# UVBox-I2C_LCD.net
KiCad netlist of a schematic drawn in EAGLE
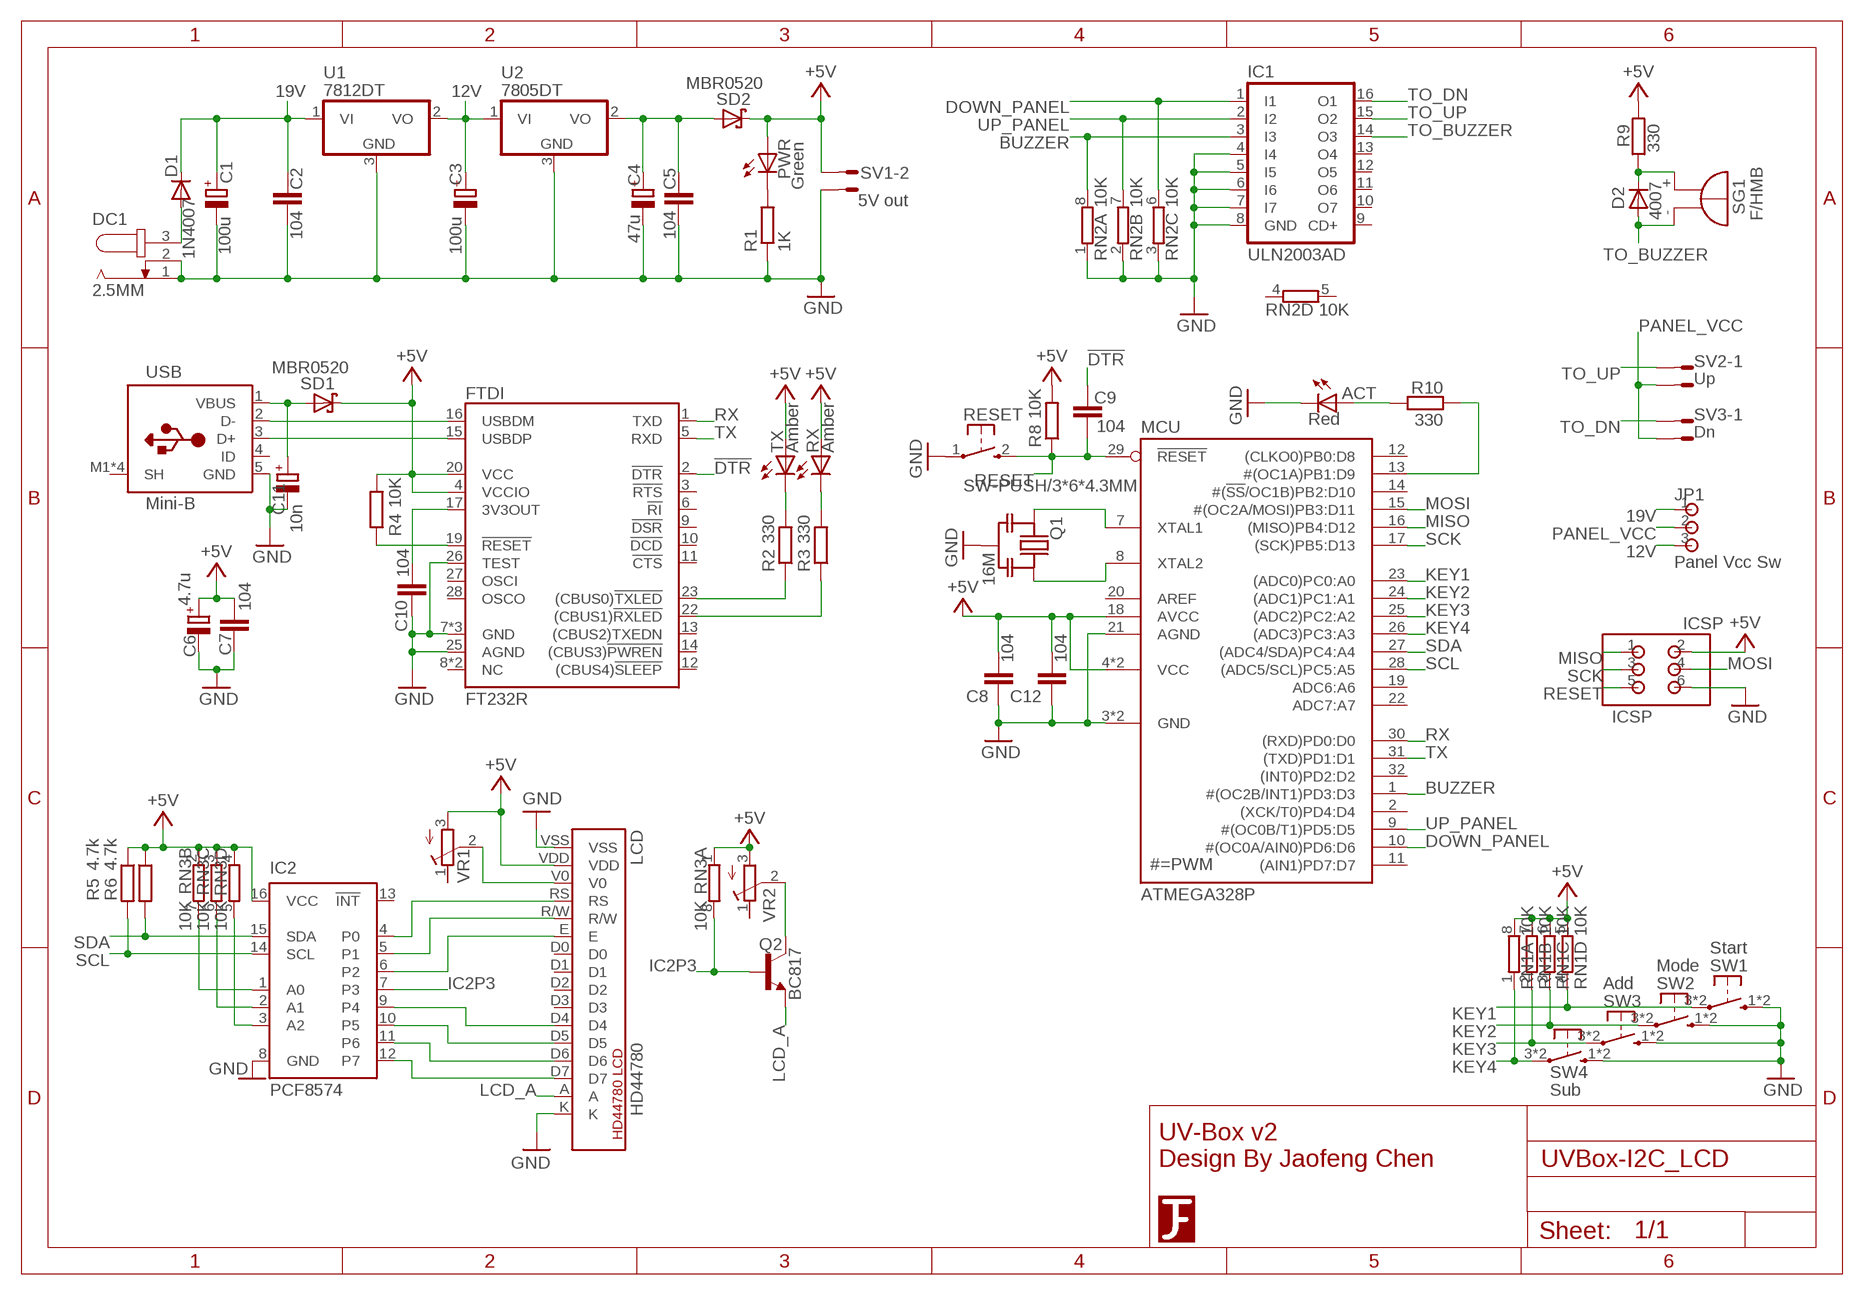
[diagram p0: schematic, sheet 1]

(export (version "E")
  (design (tool "Eeschema 10.0.6"))
  (components
    (comp (ref "ACT")
      (value "Red")
      (footprint "eagle-import:CHIPLED_0805")
      (libsource (lib "eagle-import") (part "LEDCHIPLED_0805"))
    )
    (comp (ref "C1")
      (value "100u")
      (footprint "eagle-import:140CLH-0810")
      (libsource (lib "eagle-import") (part "CPOL-EU140CLH-0810"))
    )
    (comp (ref "C2")
      (value "104")
      (footprint "eagle-import:C0805")
      (libsource (lib "eagle-import") (part "C-EUC0805"))
    )
    (comp (ref "C3")
      (value "100u")
      (footprint "eagle-import:SMC_C")
      (libsource (lib "eagle-import") (part "CPOL-EUSMCC"))
    )
    (comp (ref "C4")
      (value "47u")
      (footprint "eagle-import:SMC_C")
      (libsource (lib "eagle-import") (part "CPOL-EUSMCC"))
    )
    (comp (ref "C5")
      (value "104")
      (footprint "eagle-import:C0805")
      (libsource (lib "eagle-import") (part "C-EUC0805"))
    )
    (comp (ref "C6")
      (value "4.7u")
      (footprint "eagle-import:SMC_B")
      (libsource (lib "eagle-import") (part "CPOL-EUSMCB"))
    )
    (comp (ref "C7")
      (value "104")
      (footprint "eagle-import:C0603")
      (libsource (lib "eagle-import") (part "C-EUC0603"))
    )
    (comp (ref "C8")
      (value "104")
      (footprint "eagle-import:C0603")
      (libsource (lib "eagle-import") (part "C-EUC0603"))
    )
    (comp (ref "C9")
      (value "104")
      (footprint "eagle-import:C0603")
      (libsource (lib "eagle-import") (part "C-EUC0603"))
    )
    (comp (ref "C10")
      (value "104")
      (footprint "eagle-import:C0603")
      (libsource (lib "eagle-import") (part "C-EUC0603"))
    )
    (comp (ref "C11")
      (value "10n")
      (footprint "eagle-import:SMC_A")
      (libsource (lib "eagle-import") (part "CPOL-EUSMCA"))
    )
    (comp (ref "C12")
      (value "104")
      (footprint "eagle-import:C0603")
      (libsource (lib "eagle-import") (part "C-EUC0603"))
    )
    (comp (ref "D1")
      (value "1N4007")
      (footprint "eagle-import:DO-214AC")
      (libsource (lib "eagle-import") (part "DIODE-DO-214AC"))
    )
    (comp (ref "D2")
      (value "4007")
      (footprint "eagle-import:DO214AA")
      (libsource (lib "eagle-import") (part "DIODE-DO214AA"))
    )
    (comp (ref "DC1")
      (value "2.5MM")
      (footprint "eagle-import:SPC4078")
      (libsource (lib "eagle-import") (part "DC-JACK/2.5MM"))
    )
    (comp (ref "FTDI")
      (value "FT232R")
      (footprint "eagle-import:SSOP28")
      (libsource (lib "eagle-import") (part "FT232R"))
    )
    (comp (ref "IC1")
      (value "ULN2003AD")
      (footprint "eagle-import:SO16(R-PDSO-G16)")
      (libsource (lib "eagle-import") (part "ULN2003AD"))
    )
    (comp (ref "IC2")
      (value "PCF8574")
      (footprint "eagle-import:SO16W")
      (libsource (lib "eagle-import") (part "PCF8574/SO16W"))
    )
    (comp (ref "ICSP")
      (value "ICSP")
      (footprint "eagle-import:DIP-2.54-2X3")
      (libsource (lib "eagle-import") (part "PIN-2X3/2.54-DIP"))
    )
    (comp (ref "JP1")
      (value "Panel Vcc Sw")
      (footprint "eagle-import:DIP-2.54-1X3")
      (libsource (lib "eagle-import") (part "PIN-1X3-2.54"))
    )
    (comp (ref "LCD")
      (value "HD44780")
      (footprint "eagle-import:LCD_1602")
      (libsource (lib "eagle-import") (part "LCD-HD44780-1602"))
    )
    (comp (ref "MCU")
      (value "ATMEGA328P")
      (footprint "eagle-import:TQFP32")
      (libsource (lib "eagle-import") (part "ATMEGA-TQFP32328P"))
    )
    (comp (ref "PWR")
      (value "Green")
      (footprint "eagle-import:CHIPLED_0805")
      (libsource (lib "eagle-import") (part "LEDCHIPLED_0805"))
    )
    (comp (ref "Q1")
      (value "16M")
      (footprint "eagle-import:CSTCE")
      (libsource (lib "eagle-import") (part "CERMOSCILL-CSTCE"))
    )
    (comp (ref "Q2")
      (value "BC817")
      (footprint "eagle-import:SOT23-BEC")
      (libsource (lib "eagle-import") (part "BC817SMD-16"))
    )
    (comp (ref "R1")
      (value "1K")
      (footprint "eagle-import:R0603")
      (libsource (lib "eagle-import") (part "R-EU_R0603"))
    )
    (comp (ref "R2")
      (value "330")
      (footprint "eagle-import:R0603")
      (libsource (lib "eagle-import") (part "R-EU_R0603"))
    )
    (comp (ref "R3")
      (value "330")
      (footprint "eagle-import:R0603")
      (libsource (lib "eagle-import") (part "R-EU_R0603"))
    )
    (comp (ref "R4")
      (value "10K")
      (footprint "eagle-import:R0603")
      (libsource (lib "eagle-import") (part "R-EU_R0603"))
    )
    (comp (ref "R5")
      (value "4.7k")
      (footprint "eagle-import:R0603")
      (libsource (lib "eagle-import") (part "R-EU_R0603"))
    )
    (comp (ref "R6")
      (value "4.7k")
      (footprint "eagle-import:R0603")
      (libsource (lib "eagle-import") (part "R-EU_R0603"))
    )
    (comp (ref "R8")
      (value "10K")
      (footprint "eagle-import:R0603")
      (libsource (lib "eagle-import") (part "R-EU_R0603"))
    )
    (comp (ref "R9")
      (value "330")
      (footprint "eagle-import:R0603")
      (libsource (lib "eagle-import") (part "R-EU_R0603"))
    )
    (comp (ref "R10")
      (value "330")
      (footprint "eagle-import:R0603")
      (libsource (lib "eagle-import") (part "R-EU_R0603"))
    )
    (comp (ref "RESET")
      (value "SW-PUSH/3*6*4.3MM")
      (footprint "eagle-import:SW-3_6_4.3MM")
      (libsource (lib "eagle-import") (part "SW-PUSH/364.3MM"))
    )
    (comp (ref "RN1")
      (value "10K")
      (footprint "eagle-import:CAY16")
      (libsource (lib "eagle-import") (part "RN4R-CAY16"))
    )
    (comp (ref "RN2")
      (value "10K")
      (footprint "eagle-import:CAY16")
      (libsource (lib "eagle-import") (part "RN4R-CAY16"))
    )
    (comp (ref "RN3")
      (value "10K")
      (footprint "eagle-import:CAY16")
      (libsource (lib "eagle-import") (part "RN4R-CAY16"))
    )
    (comp (ref "RX")
      (value "Amber")
      (footprint "eagle-import:CHIPLED_0805")
      (libsource (lib "eagle-import") (part "LEDCHIPLED_0805"))
    )
    (comp (ref "SD1")
      (value "MBR0520")
      (footprint "eagle-import:SOD123")
      (libsource (lib "eagle-import") (part "SCHOTTKY"))
    )
    (comp (ref "SD2")
      (value "MBR0520")
      (footprint "eagle-import:SOD123")
      (libsource (lib "eagle-import") (part "SCHOTTKY"))
    )
    (comp (ref "SG1")
      (value "F/HMB")
      (footprint "eagle-import:F_HMB")
      (libsource (lib "eagle-import") (part "F/HMB"))
    )
    (comp (ref "SV1")
      (value "5V out")
      (footprint "eagle-import:L02P")
      (libsource (lib "eagle-import") (part "L02P"))
    )
    (comp (ref "SV2")
      (value "Up")
      (footprint "eagle-import:L02P")
      (libsource (lib "eagle-import") (part "L02P"))
    )
    (comp (ref "SV3")
      (value "Dn")
      (footprint "eagle-import:L02P")
      (libsource (lib "eagle-import") (part "L02P"))
    )
    (comp (ref "SW1")
      (value "Start")
      (footprint "eagle-import:SW-6_6_3.8MM")
      (libsource (lib "eagle-import") (part "SW-PUSH/663.8MM"))
    )
    (comp (ref "SW2")
      (value "Mode")
      (footprint "eagle-import:SW-6_6_3.8MM")
      (libsource (lib "eagle-import") (part "SW-PUSH/663.8MM"))
    )
    (comp (ref "SW3")
      (value "Add")
      (footprint "eagle-import:SW-6_6_3.8MM")
      (libsource (lib "eagle-import") (part "SW-PUSH/663.8MM"))
    )
    (comp (ref "SW4")
      (value "Sub")
      (footprint "eagle-import:SW-6_6_3.8MM")
      (libsource (lib "eagle-import") (part "SW-PUSH/663.8MM"))
    )
    (comp (ref "TX")
      (value "Amber")
      (footprint "eagle-import:CHIPLED_0805")
      (libsource (lib "eagle-import") (part "LEDCHIPLED_0805"))
    )
    (comp (ref "U$2")
      (value "LOGO-3B")
      (footprint "eagle-import:LOGO-3-B")
      (libsource (lib "eagle-import") (part "LOGO-3B"))
    )
    (comp (ref "U1")
      (value "7812DT")
      (footprint "eagle-import:TO252")
      (libsource (lib "eagle-import") (part "78DT12"))
    )
    (comp (ref "U2")
      (value "7805DT")
      (footprint "eagle-import:TO252")
      (libsource (lib "eagle-import") (part "78DT05"))
    )
    (comp (ref "USB")
      (value "Mini-B")
      (footprint "eagle-import:USB-MINI-B(NO_HOLE)")
      (libsource (lib "eagle-import") (part "USB-MINI-B/NO_HOLE"))
    )
    (comp (ref "VR1")
      (value "R-TRIMMT93XA")
      (footprint "eagle-import:RTRIMT93XA")
      (libsource (lib "eagle-import") (part "R-TRIMMT93XA"))
    )
    (comp (ref "VR2")
      (value "R-TRIMMT93XA")
      (footprint "eagle-import:RTRIMT93XA")
      (libsource (lib "eagle-import") (part "R-TRIMMT93XA"))
    )
  )
  (nets
    (net (code "1") (name "+5V") (class "Default")
      (node (ref "C12") (pin "2") (pinfunction "2_2") (pintype "passive"))
      (node (ref "C6") (pin "+") (pinfunction "+_+") (pintype "passive"))
      (node (ref "C7") (pin "1") (pinfunction "1_1") (pintype "passive"))
      (node (ref "C8") (pin "2") (pinfunction "2_2") (pintype "passive"))
      (node (ref "FTDI") (pin "20") (pinfunction "VCC_20") (pintype "power_in"))
      (node (ref "FTDI") (pin "4") (pinfunction "VCCIO_4") (pintype "power_in"))
      (node (ref "IC2") (pin "16") (pinfunction "VCC_16") (pintype "power_in"))
      (node (ref "ICSP") (pin "2") (pinfunction "2_2") (pintype "passive"))
      (node (ref "LCD") (pin "VDD") (pinfunction "VDD_VDD") (pintype "power_in"))
      (node (ref "MCU") (pin "18") (pinfunction "AVCC_18") (pintype "passive"))
      (node (ref "MCU") (pin "4") (pinfunction "VCC_4") (pintype "power_in"))
      (node (ref "MCU") (pin "6") (pinfunction "VCC_6") (pintype "power_in"))
      (node (ref "PWR") (pin "A") (pinfunction "A_A") (pintype "passive"))
      (node (ref "R4") (pin "2") (pinfunction "2_2") (pintype "passive"))
      (node (ref "R5") (pin "1") (pinfunction "1_1") (pintype "passive"))
      (node (ref "R6") (pin "1") (pinfunction "1_1") (pintype "passive"))
      (node (ref "R8") (pin "2") (pinfunction "2_2") (pintype "passive"))
      (node (ref "R9") (pin "2") (pinfunction "2_2") (pintype "passive"))
      (node (ref "RN1") (pin "5") (pinfunction "2_5") (pintype "passive"))
      (node (ref "RN1") (pin "6") (pinfunction "2_6") (pintype "passive"))
      (node (ref "RN1") (pin "7") (pinfunction "2_7") (pintype "passive"))
      (node (ref "RN1") (pin "8") (pinfunction "2_8") (pintype "passive"))
      (node (ref "RN3") (pin "1") (pinfunction "1_1") (pintype "passive"))
      (node (ref "RN3") (pin "2") (pinfunction "1_2") (pintype "passive"))
      (node (ref "RN3") (pin "3") (pinfunction "1_3") (pintype "passive"))
      (node (ref "RN3") (pin "4") (pinfunction "1_4") (pintype "passive"))
      (node (ref "RX") (pin "A") (pinfunction "A_A") (pintype "passive"))
      (node (ref "SD1") (pin "K") (pinfunction "K_K") (pintype "passive"))
      (node (ref "SD2") (pin "K") (pinfunction "K_K") (pintype "passive"))
      (node (ref "SV1") (pin "2") (pinfunction "S_2") (pintype "passive"))
      (node (ref "TX") (pin "A") (pinfunction "A_A") (pintype "passive"))
      (node (ref "VR1") (pin "3") (pinfunction "A_3") (pintype "passive"))
      (node (ref "VR2") (pin "3") (pinfunction "A_3") (pintype "passive"))
    )
    (net (code "2") (name "/12V") (class "Default")
      (node (ref "C3") (pin "+") (pinfunction "+_+") (pintype "passive"))
      (node (ref "JP1") (pin "3") (pinfunction "3_3") (pintype "passive"))
      (node (ref "U1") (pin "2") (pinfunction "VO_2") (pintype "passive"))
      (node (ref "U2") (pin "1") (pinfunction "VI_1") (pintype "input"))
    )
    (net (code "3") (name "/19V") (class "Default")
      (node (ref "C1") (pin "+") (pinfunction "+_+") (pintype "passive"))
      (node (ref "C2") (pin "1") (pinfunction "1_1") (pintype "passive"))
      (node (ref "D1") (pin "C") (pinfunction "C_C") (pintype "passive"))
      (node (ref "JP1") (pin "1") (pinfunction "1_1") (pintype "passive"))
      (node (ref "U1") (pin "1") (pinfunction "VI_1") (pintype "input"))
    )
    (net (code "4") (name "/BUZZER") (class "Default")
      (node (ref "IC1") (pin "3") (pinfunction "I3_3") (pintype "input"))
      (node (ref "MCU") (pin "1") (pinfunction "#(OC2B/INT1)PD3:D3_1") (pintype "bidirectional"))
      (node (ref "RN2") (pin "8") (pinfunction "2_8") (pintype "passive"))
    )
    (net (code "5") (name "/DOWN_PANEL") (class "Default")
      (node (ref "IC1") (pin "1") (pinfunction "I1_1") (pintype "input"))
      (node (ref "MCU") (pin "10") (pinfunction "#(OC0A/AIN0)PD6:D6_10") (pintype "bidirectional"))
      (node (ref "RN2") (pin "6") (pinfunction "2_6") (pintype "passive"))
    )
    (net (code "6") (name "/IC2P3") (class "Default")
      (node (ref "IC2") (pin "7") (pinfunction "P3_7") (pintype "bidirectional"))
      (node (ref "Q2") (pin "B") (pinfunction "B_B") (pintype "passive"))
      (node (ref "RN3") (pin "8") (pinfunction "2_8") (pintype "passive"))
    )
    (net (code "7") (name "/KEY1") (class "Default")
      (node (ref "MCU") (pin "23") (pinfunction "(ADC0)PC0:A0_23") (pintype "bidirectional"))
      (node (ref "RN1") (pin "4") (pinfunction "1_4") (pintype "passive"))
      (node (ref "SW1") (pin "3") (pinfunction "P_3") (pintype "passive"))
      (node (ref "SW1") (pin "4") (pinfunction "P_4") (pintype "passive"))
    )
    (net (code "8") (name "/KEY2") (class "Default")
      (node (ref "MCU") (pin "24") (pinfunction "(ADC1)PC1:A1_24") (pintype "bidirectional"))
      (node (ref "RN1") (pin "3") (pinfunction "1_3") (pintype "passive"))
      (node (ref "SW2") (pin "3") (pinfunction "P_3") (pintype "passive"))
      (node (ref "SW2") (pin "4") (pinfunction "P_4") (pintype "passive"))
    )
    (net (code "9") (name "/KEY3") (class "Default")
      (node (ref "MCU") (pin "25") (pinfunction "(ADC2)PC2:A2_25") (pintype "bidirectional"))
      (node (ref "RN1") (pin "2") (pinfunction "1_2") (pintype "passive"))
      (node (ref "SW3") (pin "3") (pinfunction "P_3") (pintype "passive"))
      (node (ref "SW3") (pin "4") (pinfunction "P_4") (pintype "passive"))
    )
    (net (code "10") (name "/KEY4") (class "Default")
      (node (ref "MCU") (pin "26") (pinfunction "(ADC3)PC3:A3_26") (pintype "bidirectional"))
      (node (ref "RN1") (pin "1") (pinfunction "1_1") (pintype "passive"))
      (node (ref "SW4") (pin "3") (pinfunction "P_3") (pintype "passive"))
      (node (ref "SW4") (pin "4") (pinfunction "P_4") (pintype "passive"))
    )
    (net (code "11") (name "/LCD_A") (class "Default")
      (node (ref "LCD") (pin "A") (pinfunction "A_A") (pintype "passive"))
      (node (ref "Q2") (pin "E") (pinfunction "E_E") (pintype "passive"))
    )
    (net (code "12") (name "/MISO") (class "Default")
      (node (ref "ICSP") (pin "1") (pinfunction "1_1") (pintype "passive"))
      (node (ref "MCU") (pin "16") (pinfunction "(MISO)PB4:D12_16") (pintype "bidirectional"))
    )
    (net (code "13") (name "/MOSI") (class "Default")
      (node (ref "ICSP") (pin "4") (pinfunction "4_4") (pintype "passive"))
      (node (ref "MCU") (pin "15") (pinfunction "#(OC2A/MOSI)PB3:D11_15") (pintype "bidirectional"))
    )
    (net (code "14") (name "/PANEL_VCC") (class "Default")
      (node (ref "JP1") (pin "2") (pinfunction "2_2") (pintype "passive"))
      (node (ref "SV2") (pin "2") (pinfunction "S_2") (pintype "passive"))
      (node (ref "SV3") (pin "2") (pinfunction "S_2") (pintype "passive"))
    )
    (net (code "15") (name "/RESET") (class "Default")
      (node (ref "C9") (pin "1") (pinfunction "1_1") (pintype "passive"))
      (node (ref "ICSP") (pin "5") (pinfunction "5_5") (pintype "passive"))
      (node (ref "MCU") (pin "29") (pinfunction "~{RESET}_29") (pintype "input"))
      (node (ref "R8") (pin "1") (pinfunction "1_1") (pintype "passive"))
      (node (ref "RESET") (pin "2") (pinfunction "S_2") (pintype "passive"))
    )
    (net (code "16") (name "/RX") (class "Default")
      (node (ref "FTDI") (pin "1") (pinfunction "TXD_1") (pintype "output"))
      (node (ref "MCU") (pin "30") (pinfunction "(RXD)PD0:D0_30") (pintype "bidirectional"))
    )
    (net (code "17") (name "/SCK") (class "Default")
      (node (ref "ICSP") (pin "3") (pinfunction "3_3") (pintype "passive"))
      (node (ref "MCU") (pin "17") (pinfunction "(SCK)PB5:D13_17") (pintype "bidirectional"))
    )
    (net (code "18") (name "/SCL") (class "Default")
      (node (ref "IC2") (pin "14") (pinfunction "SCL_14") (pintype "input"))
      (node (ref "MCU") (pin "28") (pinfunction "(ADC5/SCL)PC5:A5_28") (pintype "bidirectional"))
      (node (ref "R5") (pin "2") (pinfunction "2_2") (pintype "passive"))
    )
    (net (code "19") (name "/SDA") (class "Default")
      (node (ref "IC2") (pin "15") (pinfunction "SDA_15") (pintype "bidirectional"))
      (node (ref "MCU") (pin "27") (pinfunction "(ADC4/SDA)PC4:A4_27") (pintype "bidirectional"))
      (node (ref "R6") (pin "2") (pinfunction "2_2") (pintype "passive"))
    )
    (net (code "20") (name "/TO_BUZZER") (class "Default")
      (node (ref "D2") (pin "A") (pinfunction "A_A") (pintype "passive"))
      (node (ref "IC1") (pin "14") (pinfunction "O3_14") (pintype "open_collector"))
      (node (ref "SG1") (pin "-") (pinfunction "-_-") (pintype "passive"))
    )
    (net (code "21") (name "/TO_DN") (class "Default")
      (node (ref "IC1") (pin "16") (pinfunction "O1_16") (pintype "open_collector"))
      (node (ref "SV3") (pin "1") (pinfunction "S_1") (pintype "passive"))
    )
    (net (code "22") (name "/TO_UP") (class "Default")
      (node (ref "IC1") (pin "15") (pinfunction "O2_15") (pintype "open_collector"))
      (node (ref "SV2") (pin "1") (pinfunction "S_1") (pintype "passive"))
    )
    (net (code "23") (name "/TX") (class "Default")
      (node (ref "FTDI") (pin "5") (pinfunction "RXD_5") (pintype "input"))
      (node (ref "MCU") (pin "31") (pinfunction "(TXD)PD1:D1_31") (pintype "bidirectional"))
    )
    (net (code "24") (name "/UP_PANEL") (class "Default")
      (node (ref "IC1") (pin "2") (pinfunction "I2_2") (pintype "input"))
      (node (ref "MCU") (pin "9") (pinfunction "#(OC0B/T1)PD5:D5_9") (pintype "bidirectional"))
      (node (ref "RN2") (pin "7") (pinfunction "2_7") (pintype "passive"))
    )
    (net (code "25") (name "/~{DTR}") (class "Default")
      (node (ref "C9") (pin "2") (pinfunction "2_2") (pintype "passive"))
      (node (ref "FTDI") (pin "2") (pinfunction "~{DTR}_2") (pintype "output"))
    )
    (net (code "26") (name "GND") (class "Default")
      (node (ref "ACT") (pin "C") (pinfunction "C_C") (pintype "passive"))
      (node (ref "C1") (pin "-") (pinfunction "-_-") (pintype "passive"))
      (node (ref "C10") (pin "1") (pinfunction "1_1") (pintype "passive"))
      (node (ref "C11") (pin "-") (pinfunction "-_-") (pintype "passive"))
      (node (ref "C12") (pin "1") (pinfunction "1_1") (pintype "passive"))
      (node (ref "C2") (pin "2") (pinfunction "2_2") (pintype "passive"))
      (node (ref "C3") (pin "-") (pinfunction "-_-") (pintype "passive"))
      (node (ref "C4") (pin "-") (pinfunction "-_-") (pintype "passive"))
      (node (ref "C5") (pin "2") (pinfunction "2_2") (pintype "passive"))
      (node (ref "C6") (pin "-") (pinfunction "-_-") (pintype "passive"))
      (node (ref "C7") (pin "2") (pinfunction "2_2") (pintype "passive"))
      (node (ref "C8") (pin "1") (pinfunction "1_1") (pintype "passive"))
      (node (ref "DC1") (pin "1") (pinfunction "1_1") (pintype "passive"))
      (node (ref "DC1") (pin "2") (pinfunction "2_2") (pintype "passive"))
      (node (ref "FTDI") (pin "18") (pinfunction "GND_18") (pintype "power_in"))
      (node (ref "FTDI") (pin "21") (pinfunction "GND_21") (pintype "power_in"))
      (node (ref "FTDI") (pin "25") (pinfunction "AGND_25") (pintype "power_in"))
      (node (ref "FTDI") (pin "26") (pinfunction "TEST_26") (pintype "input"))
      (node (ref "FTDI") (pin "7") (pinfunction "GND_7") (pintype "power_in"))
      (node (ref "IC1") (pin "4") (pinfunction "I4_4") (pintype "input"))
      (node (ref "IC1") (pin "5") (pinfunction "I5_5") (pintype "input"))
      (node (ref "IC1") (pin "6") (pinfunction "I6_6") (pintype "input"))
      (node (ref "IC1") (pin "7") (pinfunction "I7_7") (pintype "input"))
      (node (ref "IC1") (pin "8") (pinfunction "GND_8") (pintype "power_in"))
      (node (ref "IC2") (pin "8") (pinfunction "GND_8") (pintype "power_in"))
      (node (ref "ICSP") (pin "6") (pinfunction "6_6") (pintype "passive"))
      (node (ref "LCD") (pin "K") (pinfunction "K_K") (pintype "passive"))
      (node (ref "LCD") (pin "VSS") (pinfunction "VSS_VSS") (pintype "power_in"))
      (node (ref "MCU") (pin "21") (pinfunction "AGND_21") (pintype "passive"))
      (node (ref "MCU") (pin "3") (pinfunction "GND_3") (pintype "power_in"))
      (node (ref "MCU") (pin "5") (pinfunction "GND_5") (pintype "power_in"))
      (node (ref "Q1") (pin "2") (pinfunction "GND_2") (pintype "bidirectional"))
      (node (ref "R1") (pin "1") (pinfunction "1_1") (pintype "passive"))
      (node (ref "RESET") (pin "1") (pinfunction "P_1") (pintype "passive"))
      (node (ref "RN2") (pin "1") (pinfunction "1_1") (pintype "passive"))
      (node (ref "RN2") (pin "2") (pinfunction "1_2") (pintype "passive"))
      (node (ref "RN2") (pin "3") (pinfunction "1_3") (pintype "passive"))
      (node (ref "SV1") (pin "1") (pinfunction "S_1") (pintype "passive"))
      (node (ref "SW1") (pin "1") (pinfunction "S_1") (pintype "passive"))
      (node (ref "SW1") (pin "2") (pinfunction "S_2") (pintype "passive"))
      (node (ref "SW2") (pin "1") (pinfunction "S_1") (pintype "passive"))
      (node (ref "SW2") (pin "2") (pinfunction "S_2") (pintype "passive"))
      (node (ref "SW3") (pin "1") (pinfunction "S_1") (pintype "passive"))
      (node (ref "SW3") (pin "2") (pinfunction "S_2") (pintype "passive"))
      (node (ref "SW4") (pin "1") (pinfunction "S_1") (pintype "passive"))
      (node (ref "SW4") (pin "2") (pinfunction "S_2") (pintype "passive"))
      (node (ref "U1") (pin "3") (pinfunction "GND_3") (pintype "passive"))
      (node (ref "U2") (pin "3") (pinfunction "GND_3") (pintype "passive"))
      (node (ref "USB") (pin "5") (pinfunction "GND_5") (pintype "power_in"))
    )
    (net (code "27") (name "Net-(ACT-PadA)") (class "Default")
      (node (ref "ACT") (pin "A") (pinfunction "A_A") (pintype "passive"))
      (node (ref "R10") (pin "2") (pinfunction "2_2") (pintype "passive"))
    )
    (net (code "28") (name "Net-(D1-PadA)") (class "Default")
      (node (ref "D1") (pin "A") (pinfunction "A_A") (pintype "passive"))
      (node (ref "DC1") (pin "3") (pinfunction "3_3") (pintype "passive"))
    )
    (net (code "29") (name "Net-(D2-PadC)") (class "Default")
      (node (ref "D2") (pin "C") (pinfunction "C_C") (pintype "passive"))
      (node (ref "R9") (pin "1") (pinfunction "1_1") (pintype "passive"))
      (node (ref "SG1") (pin "+") (pinfunction "+_+") (pintype "passive"))
    )
    (net (code "30") (name "Net-(FTDI-(CBUS0)~{TXLED})") (class "Default")
      (node (ref "FTDI") (pin "23") (pinfunction "(CBUS0)~{TXLED}_23") (pintype "bidirectional"))
      (node (ref "R2") (pin "1") (pinfunction "1_1") (pintype "passive"))
    )
    (net (code "31") (name "Net-(FTDI-(CBUS1)~{RXLED})") (class "Default")
      (node (ref "FTDI") (pin "22") (pinfunction "(CBUS1)~{RXLED}_22") (pintype "bidirectional"))
      (node (ref "R3") (pin "1") (pinfunction "1_1") (pintype "passive"))
    )
    (net (code "32") (name "Net-(FTDI-3V3OUT)") (class "Default")
      (node (ref "C10") (pin "2") (pinfunction "2_2") (pintype "passive"))
      (node (ref "FTDI") (pin "17") (pinfunction "3V3OUT_17") (pintype "output"))
    )
    (net (code "33") (name "Net-(FTDI-USBDM)") (class "Default")
      (node (ref "FTDI") (pin "16") (pinfunction "USBDM_16") (pintype "bidirectional"))
      (node (ref "USB") (pin "2") (pinfunction "D-_2") (pintype "bidirectional"))
    )
    (net (code "34") (name "Net-(FTDI-USBDP)") (class "Default")
      (node (ref "FTDI") (pin "15") (pinfunction "USBDP_15") (pintype "bidirectional"))
      (node (ref "USB") (pin "3") (pinfunction "D+_3") (pintype "bidirectional"))
    )
    (net (code "35") (name "Net-(FTDI-~{RESET})") (class "Default")
      (node (ref "FTDI") (pin "19") (pinfunction "~{RESET}_19") (pintype "input"))
      (node (ref "R4") (pin "1") (pinfunction "1_1") (pintype "passive"))
    )
    (net (code "36") (name "Net-(IC2-A0)") (class "Default")
      (node (ref "IC2") (pin "1") (pinfunction "A0_1") (pintype "input"))
      (node (ref "RN3") (pin "7") (pinfunction "2_7") (pintype "passive"))
    )
    (net (code "37") (name "Net-(IC2-A1)") (class "Default")
      (node (ref "IC2") (pin "2") (pinfunction "A1_2") (pintype "input"))
      (node (ref "RN3") (pin "6") (pinfunction "2_6") (pintype "passive"))
    )
    (net (code "38") (name "Net-(IC2-A2)") (class "Default")
      (node (ref "IC2") (pin "3") (pinfunction "A2_3") (pintype "input"))
      (node (ref "RN3") (pin "5") (pinfunction "2_5") (pintype "passive"))
    )
    (net (code "39") (name "Net-(IC2-P0)") (class "Default")
      (node (ref "IC2") (pin "4") (pinfunction "P0_4") (pintype "bidirectional"))
      (node (ref "LCD") (pin "RS") (pinfunction "RS_RS") (pintype "bidirectional"))
    )
    (net (code "40") (name "Net-(IC2-P1)") (class "Default")
      (node (ref "IC2") (pin "5") (pinfunction "P1_5") (pintype "bidirectional"))
      (node (ref "LCD") (pin "R/W") (pinfunction "R/W_R/W") (pintype "bidirectional"))
    )
    (net (code "41") (name "Net-(IC2-P2)") (class "Default")
      (node (ref "IC2") (pin "6") (pinfunction "P2_6") (pintype "bidirectional"))
      (node (ref "LCD") (pin "E") (pinfunction "E_E") (pintype "bidirectional"))
    )
    (net (code "42") (name "Net-(IC2-P4)") (class "Default")
      (node (ref "IC2") (pin "9") (pinfunction "P4_9") (pintype "bidirectional"))
      (node (ref "LCD") (pin "D4") (pinfunction "D4_D4") (pintype "input"))
    )
    (net (code "43") (name "Net-(IC2-P5)") (class "Default")
      (node (ref "IC2") (pin "10") (pinfunction "P5_10") (pintype "bidirectional"))
      (node (ref "LCD") (pin "D5") (pinfunction "D5_D5") (pintype "input"))
    )
    (net (code "44") (name "Net-(IC2-P6)") (class "Default")
      (node (ref "IC2") (pin "11") (pinfunction "P6_11") (pintype "bidirectional"))
      (node (ref "LCD") (pin "D6") (pinfunction "D6_D6") (pintype "input"))
    )
    (net (code "45") (name "Net-(IC2-P7)") (class "Default")
      (node (ref "IC2") (pin "12") (pinfunction "P7_12") (pintype "bidirectional"))
      (node (ref "LCD") (pin "D7") (pinfunction "D7_D7") (pintype "input"))
    )
    (net (code "46") (name "Net-(MCU-#(OC1A)PB1:D9)") (class "Default")
      (node (ref "MCU") (pin "13") (pinfunction "#(OC1A)PB1:D9_13") (pintype "bidirectional"))
      (node (ref "R10") (pin "1") (pinfunction "1_1") (pintype "passive"))
    )
    (net (code "47") (name "Net-(MCU-XTAL1)") (class "Default")
      (node (ref "MCU") (pin "7") (pinfunction "XTAL1_7") (pintype "bidirectional"))
      (node (ref "Q1") (pin "1") (pinfunction "IN_1") (pintype "bidirectional"))
    )
    (net (code "48") (name "Net-(MCU-XTAL2)") (class "Default")
      (node (ref "MCU") (pin "8") (pinfunction "XTAL2_8") (pintype "bidirectional"))
      (node (ref "Q1") (pin "3") (pinfunction "OUT_3") (pintype "bidirectional"))
    )
    (net (code "49") (name "Net-(PWR-PadC)") (class "Default")
      (node (ref "PWR") (pin "C") (pinfunction "C_C") (pintype "passive"))
      (node (ref "R1") (pin "2") (pinfunction "2_2") (pintype "passive"))
    )
    (net (code "50") (name "Net-(R2-Pad2)") (class "Default")
      (node (ref "R2") (pin "2") (pinfunction "2_2") (pintype "passive"))
      (node (ref "TX") (pin "C") (pinfunction "C_C") (pintype "passive"))
    )
    (net (code "51") (name "Net-(R3-Pad2)") (class "Default")
      (node (ref "R3") (pin "2") (pinfunction "2_2") (pintype "passive"))
      (node (ref "RX") (pin "C") (pinfunction "C_C") (pintype "passive"))
    )
    (net (code "52") (name "Net-(U2-VO)") (class "Default")
      (node (ref "C4") (pin "+") (pinfunction "+_+") (pintype "passive"))
      (node (ref "C5") (pin "1") (pinfunction "1_1") (pintype "passive"))
      (node (ref "SD2") (pin "A") (pinfunction "A_A") (pintype "passive"))
      (node (ref "U2") (pin "2") (pinfunction "VO_2") (pintype "passive"))
    )
    (net (code "53") (name "Net-(USB-VBUS)") (class "Default")
      (node (ref "C11") (pin "+") (pinfunction "+_+") (pintype "passive"))
      (node (ref "SD1") (pin "A") (pinfunction "A_A") (pintype "passive"))
      (node (ref "USB") (pin "1") (pinfunction "VBUS_1") (pintype "power_in"))
    )
    (net (code "54") (name "Net-(VR1-S)") (class "Default")
      (node (ref "LCD") (pin "V0") (pinfunction "V0_V0") (pintype "passive"))
      (node (ref "VR1") (pin "2") (pinfunction "S_2") (pintype "passive"))
    )
    (net (code "55") (name "Net-(VR2-S)") (class "Default")
      (node (ref "Q2") (pin "C") (pinfunction "C_C") (pintype "passive"))
      (node (ref "VR2") (pin "2") (pinfunction "S_2") (pintype "passive"))
    )
    (net (code "56") (name "unconnected-(FTDI-(CBUS2)TXEDN-Pad13)") (class "Default")
      (node (ref "FTDI") (pin "13") (pinfunction "(CBUS2)TXEDN_13") (pintype "bidirectional"))
    )
    (net (code "57") (name "unconnected-(FTDI-(CBUS3)~{PWREN}-Pad14)") (class "Default")
      (node (ref "FTDI") (pin "14") (pinfunction "(CBUS3)~{PWREN}_14") (pintype "bidirectional"))
    )
    (net (code "58") (name "unconnected-(FTDI-(CBUS4)~{SLEEP}-Pad12)") (class "Default")
      (node (ref "FTDI") (pin "12") (pinfunction "(CBUS4)~{SLEEP}_12") (pintype "bidirectional"))
    )
    (net (code "59") (name "unconnected-(FTDI-NC-Pad8)") (class "Default")
      (node (ref "FTDI") (pin "8") (pinfunction "NC_8") (pintype "no_connect"))
    )
    (net (code "60") (name "unconnected-(FTDI-NC-Pad24)") (class "Default")
      (node (ref "FTDI") (pin "24") (pinfunction "NC_24") (pintype "no_connect"))
    )
    (net (code "61") (name "unconnected-(FTDI-OSCI-Pad27)") (class "Default")
      (node (ref "FTDI") (pin "27") (pinfunction "OSCI_27") (pintype "input"))
    )
    (net (code "62") (name "unconnected-(FTDI-OSCO-Pad28)") (class "Default")
      (node (ref "FTDI") (pin "28") (pinfunction "OSCO_28") (pintype "output"))
    )
    (net (code "63") (name "unconnected-(FTDI-~{CTS}-Pad11)") (class "Default")
      (node (ref "FTDI") (pin "11") (pinfunction "~{CTS}_11") (pintype "input"))
    )
    (net (code "64") (name "unconnected-(FTDI-~{DCD}-Pad10)") (class "Default")
      (node (ref "FTDI") (pin "10") (pinfunction "~{DCD}_10") (pintype "input"))
    )
    (net (code "65") (name "unconnected-(FTDI-~{DSR}-Pad9)") (class "Default")
      (node (ref "FTDI") (pin "9") (pinfunction "~{DSR}_9") (pintype "input"))
    )
    (net (code "66") (name "unconnected-(FTDI-~{RI}-Pad6)") (class "Default")
      (node (ref "FTDI") (pin "6") (pinfunction "~{RI}_6") (pintype "input"))
    )
    (net (code "67") (name "unconnected-(FTDI-~{RTS}-Pad3)") (class "Default")
      (node (ref "FTDI") (pin "3") (pinfunction "~{RTS}_3") (pintype "output"))
    )
    (net (code "68") (name "unconnected-(IC1-CD+-Pad9)") (class "Default")
      (node (ref "IC1") (pin "9") (pinfunction "CD+_9") (pintype "passive"))
    )
    (net (code "69") (name "unconnected-(IC1-O4-Pad13)") (class "Default")
      (node (ref "IC1") (pin "13") (pinfunction "O4_13") (pintype "open_collector"))
    )
    (net (code "70") (name "unconnected-(IC1-O5-Pad12)") (class "Default")
      (node (ref "IC1") (pin "12") (pinfunction "O5_12") (pintype "open_collector"))
    )
    (net (code "71") (name "unconnected-(IC1-O6-Pad11)") (class "Default")
      (node (ref "IC1") (pin "11") (pinfunction "O6_11") (pintype "open_collector"))
    )
    (net (code "72") (name "unconnected-(IC1-O7-Pad10)") (class "Default")
      (node (ref "IC1") (pin "10") (pinfunction "O7_10") (pintype "open_collector"))
    )
    (net (code "73") (name "unconnected-(IC2-~{INT}-Pad13)") (class "Default")
      (node (ref "IC2") (pin "13") (pinfunction "~{INT}_13") (pintype "output"))
    )
    (net (code "74") (name "unconnected-(LCD-P$1-PadP$2)") (class "Default")
      (node (ref "LCD") (pin "P$2") (pinfunction "P$1_P$2") (pintype "no_connect"))
    )
    (net (code "75") (name "unconnected-(LCD-P$1-PadP$3)") (class "Default")
      (node (ref "LCD") (pin "P$3") (pinfunction "P$1_P$3") (pintype "no_connect"))
    )
    (net (code "76") (name "unconnected-(LCD-P$1-PadP$4)") (class "Default")
      (node (ref "LCD") (pin "P$4") (pinfunction "P$1_P$4") (pintype "no_connect"))
    )
    (net (code "77") (name "unconnected-(LCD-PadD0)") (class "Default")
      (node (ref "LCD") (pin "D0") (pinfunction "D0_D0") (pintype "input"))
    )
    (net (code "78") (name "unconnected-(LCD-PadD1)") (class "Default")
      (node (ref "LCD") (pin "D1") (pinfunction "D1_D1") (pintype "input"))
    )
    (net (code "79") (name "unconnected-(LCD-PadD2)") (class "Default")
      (node (ref "LCD") (pin "D2") (pinfunction "D2_D2") (pintype "input"))
    )
    (net (code "80") (name "unconnected-(LCD-PadD3)") (class "Default")
      (node (ref "LCD") (pin "D3") (pinfunction "D3_D3") (pintype "input"))
    )
    (net (code "81") (name "unconnected-(LCD-PadP$1)") (class "Default")
      (node (ref "LCD") (pin "P$1") (pinfunction "P$1_P$1") (pintype "no_connect"))
    )
    (net (code "82") (name "unconnected-(MCU-#(~{SS}{slash}OC1B)PB2:D10-Pad14)") (class "Default")
      (node (ref "MCU") (pin "14") (pinfunction "#(~{SS}/OC1B)PB2:D10_14") (pintype "bidirectional"))
    )
    (net (code "83") (name "unconnected-(MCU-(AIN1)PD7:D7-Pad11)") (class "Default")
      (node (ref "MCU") (pin "11") (pinfunction "(AIN1)PD7:D7_11") (pintype "bidirectional"))
    )
    (net (code "84") (name "unconnected-(MCU-(CLKO0)PB0:D8-Pad12)") (class "Default")
      (node (ref "MCU") (pin "12") (pinfunction "(CLKO0)PB0:D8_12") (pintype "bidirectional"))
    )
    (net (code "85") (name "unconnected-(MCU-(INT0)PD2:D2-Pad32)") (class "Default")
      (node (ref "MCU") (pin "32") (pinfunction "(INT0)PD2:D2_32") (pintype "bidirectional"))
    )
    (net (code "86") (name "unconnected-(MCU-(XCK{slash}T0)PD4:D4-Pad2)") (class "Default")
      (node (ref "MCU") (pin "2") (pinfunction "(XCK/T0)PD4:D4_2") (pintype "bidirectional"))
    )
    (net (code "87") (name "unconnected-(MCU-ADC6:A6-Pad19)") (class "Default")
      (node (ref "MCU") (pin "19") (pinfunction "ADC6:A6_19") (pintype "bidirectional"))
    )
    (net (code "88") (name "unconnected-(MCU-ADC7:A7-Pad22)") (class "Default")
      (node (ref "MCU") (pin "22") (pinfunction "ADC7:A7_22") (pintype "bidirectional"))
    )
    (net (code "89") (name "unconnected-(MCU-AREF-Pad20)") (class "Default")
      (node (ref "MCU") (pin "20") (pinfunction "AREF_20") (pintype "passive"))
    )
    (net (code "90") (name "unconnected-(RN2D-1-Pad4)") (class "Default")
      (node (ref "RN2") (pin "4") (pinfunction "1_4") (pintype "passive"))
    )
    (net (code "91") (name "unconnected-(RN2D-2-Pad5)") (class "Default")
      (node (ref "RN2") (pin "5") (pinfunction "2_5") (pintype "passive"))
    )
    (net (code "92") (name "unconnected-(USB-ID-Pad4)") (class "Default")
      (node (ref "USB") (pin "4") (pinfunction "ID_4") (pintype "bidirectional"))
    )
    (net (code "93") (name "unconnected-(USB-SH-PadM1)") (class "Default")
      (node (ref "USB") (pin "M1") (pinfunction "SH_M1") (pintype "no_connect"))
    )
    (net (code "94") (name "unconnected-(USB-SH-PadM2)") (class "Default")
      (node (ref "USB") (pin "M2") (pinfunction "SH_M2") (pintype "no_connect"))
    )
    (net (code "95") (name "unconnected-(USB-SH-PadM3)") (class "Default")
      (node (ref "USB") (pin "M3") (pinfunction "SH_M3") (pintype "no_connect"))
    )
    (net (code "96") (name "unconnected-(USB-SH-PadM4)") (class "Default")
      (node (ref "USB") (pin "M4") (pinfunction "SH_M4") (pintype "no_connect"))
    )
    (net (code "97") (name "unconnected-(VR1-E-Pad1)") (class "Default")
      (node (ref "VR1") (pin "1") (pinfunction "E_1") (pintype "passive"))
    )
    (net (code "98") (name "unconnected-(VR2-E-Pad1)") (class "Default")
      (node (ref "VR2") (pin "1") (pinfunction "E_1") (pintype "passive"))
    )
  )
)
